# Meter-V2.net
KiCad netlist of a schematic drawn in EAGLE
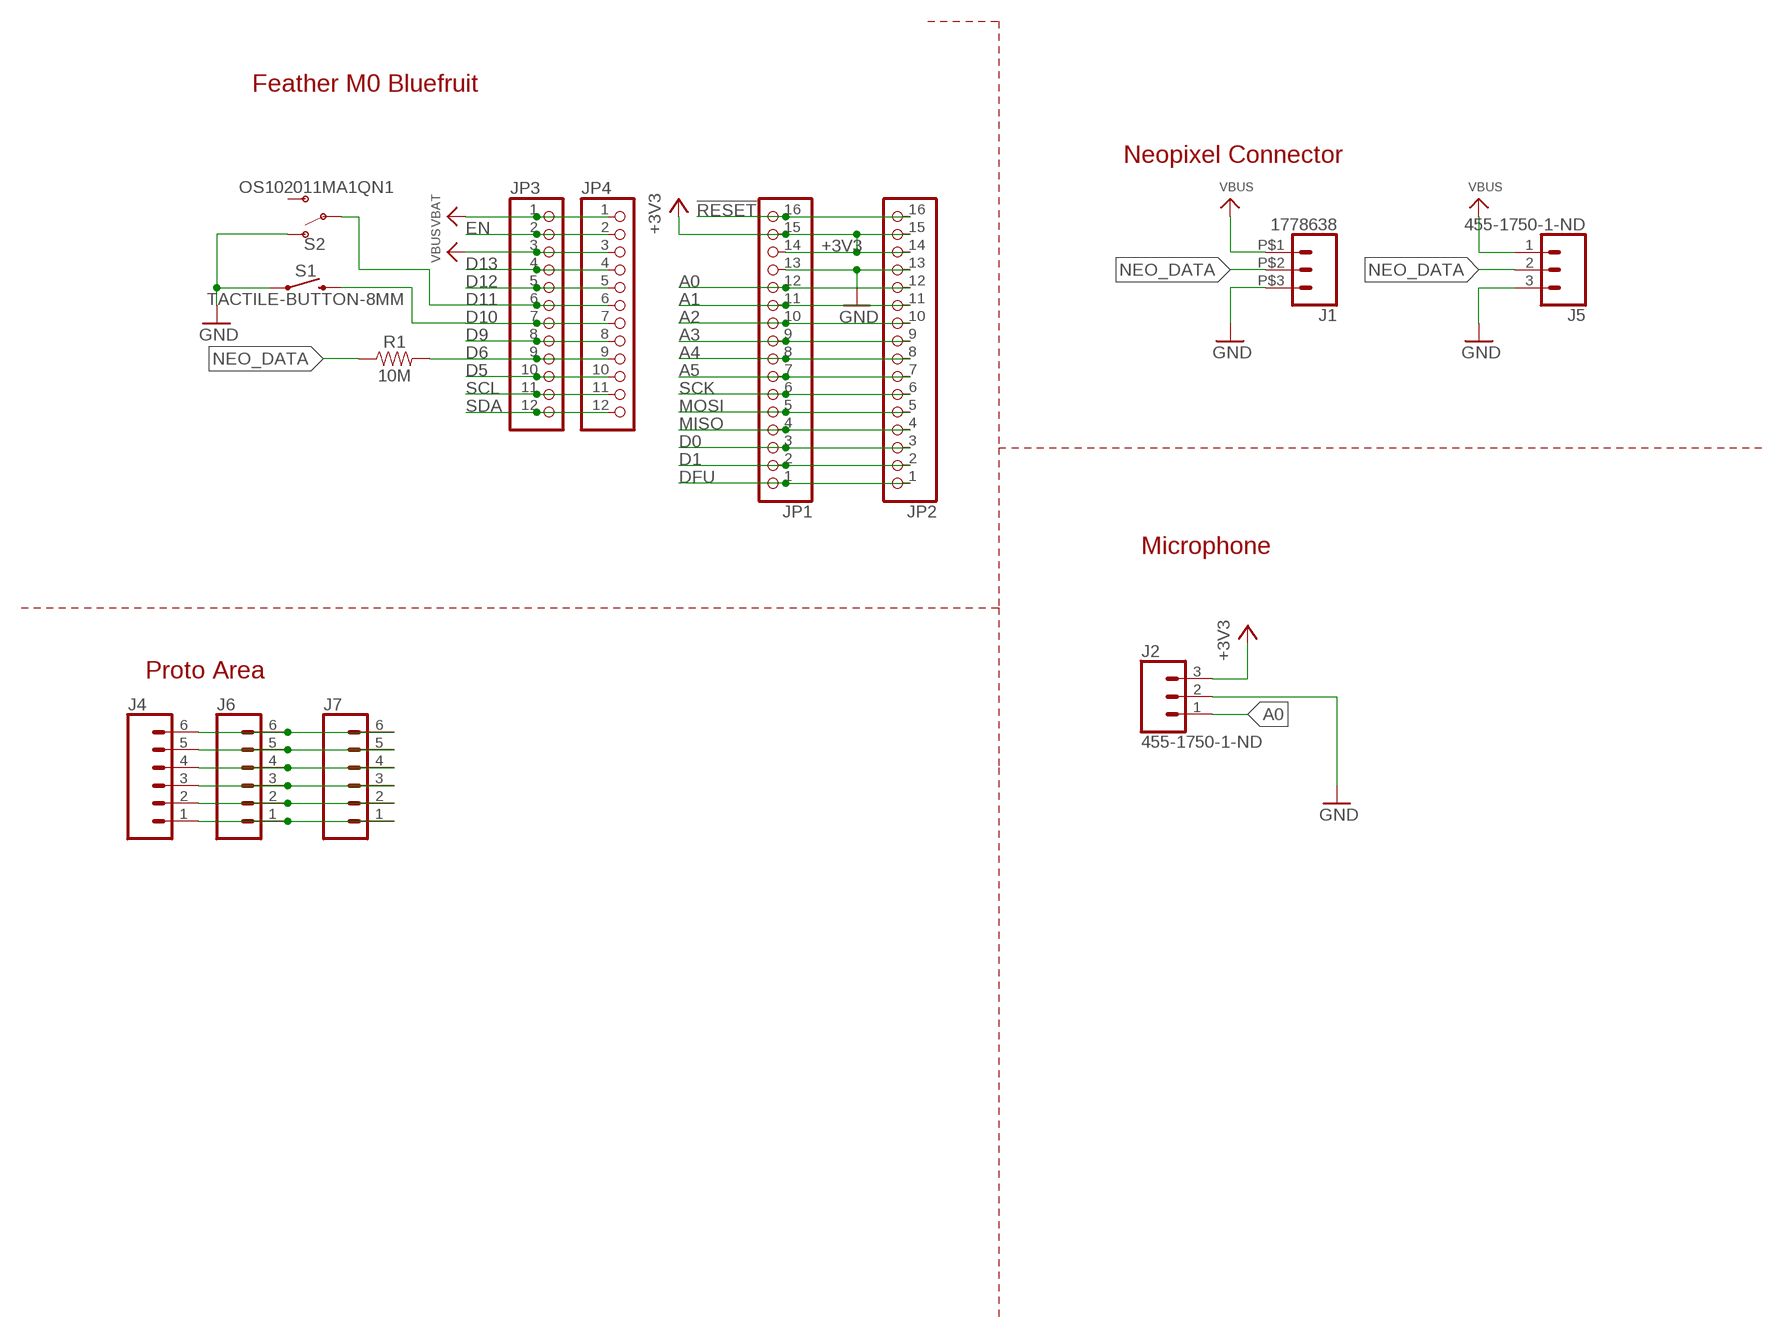
[diagram p0: schematic, sheet 1]

(export (version "E")
  (design (tool "Eeschema 10.0.6"))
  (components
    (comp (ref "J1")
      (value "1778638")
      (footprint "eagle-import:1778638")
      (libsource (lib "eagle-import") (part "1778638"))
    )
    (comp (ref "J2")
      (value "455-1750-1-ND")
      (footprint "eagle-import:1X03")
      (libsource (lib "eagle-import") (part "CONN_03"))
    )
    (comp (ref "J4")
      (value "CONN_06NO_SILK_NO_POP")
      (footprint "eagle-import:1X06_NO_SILK")
      (libsource (lib "eagle-import") (part "CONN_06NO_SILK_NO_POP"))
    )
    (comp (ref "J5")
      (value "455-1750-1-ND")
      (footprint "eagle-import:1X03")
      (libsource (lib "eagle-import") (part "CONN_03"))
    )
    (comp (ref "J6")
      (value "CONN_06NO_SILK_NO_POP")
      (footprint "eagle-import:1X06_NO_SILK")
      (libsource (lib "eagle-import") (part "CONN_06NO_SILK_NO_POP"))
    )
    (comp (ref "J7")
      (value "CONN_06NO_SILK_NO_POP")
      (footprint "eagle-import:1X06_NO_SILK")
      (libsource (lib "eagle-import") (part "CONN_06NO_SILK_NO_POP"))
    )
    (comp (ref "JP1")
      (value "HEADER-1X16ROUND")
      (footprint "eagle-import:1X16_ROUND")
      (libsource (lib "eagle-import") (part "HEADER-1X16ROUND"))
    )
    (comp (ref "JP2")
      (value "HEADER-1X16ROUND")
      (footprint "eagle-import:1X16_ROUND")
      (libsource (lib "eagle-import") (part "HEADER-1X16ROUND"))
    )
    (comp (ref "JP3")
      (value "HEADER-1X12")
      (footprint "eagle-import:1X12_ROUND")
      (libsource (lib "eagle-import") (part "HEADER-1X12"))
    )
    (comp (ref "JP4")
      (value "HEADER-1X12")
      (footprint "eagle-import:1X12_ROUND")
      (libsource (lib "eagle-import") (part "HEADER-1X12"))
    )
    (comp (ref "R1")
      (value "10M")
      (footprint "eagle-import:AXIAL-0.3")
      (libsource (lib "eagle-import") (part "10MOHM-HORIZ-1/4W-5%"))
    )
    (comp (ref "S1")
      (value "TACTILE-BUTTON-8MM")
      (footprint "eagle-import:BUTTON-8MM")
      (libsource (lib "eagle-import") (part "TACTILE-BUTTON-8MM"))
    )
    (comp (ref "S2")
      (value "OS102011MA1QN1")
      (footprint "eagle-import:OS102011MA1QN1")
      (libsource (lib "eagle-import") (part "OS102011MA1QN1"))
    )
  )
  (nets
    (net (code "1") (name "+3V3") (class "Default")
      (node (ref "J2") (pin "3") (pinfunction "3_3") (pintype "passive"))
      (node (ref "JP1") (pin "14") (pinfunction "14_14") (pintype "passive"))
      (node (ref "JP1") (pin "15") (pinfunction "15_15") (pintype "passive"))
      (node (ref "JP2") (pin "14") (pinfunction "14_14") (pintype "passive"))
      (node (ref "JP2") (pin "15") (pinfunction "15_15") (pintype "passive"))
    )
    (net (code "2") (name "/A1") (class "Default")
      (node (ref "JP1") (pin "11") (pinfunction "11_11") (pintype "passive"))
      (node (ref "JP2") (pin "11") (pinfunction "11_11") (pintype "passive"))
    )
    (net (code "3") (name "/A2") (class "Default")
      (node (ref "JP1") (pin "10") (pinfunction "10_10") (pintype "passive"))
      (node (ref "JP2") (pin "10") (pinfunction "10_10") (pintype "passive"))
    )
    (net (code "4") (name "/A3") (class "Default")
      (node (ref "JP1") (pin "9") (pinfunction "9_9") (pintype "passive"))
      (node (ref "JP2") (pin "9") (pinfunction "9_9") (pintype "passive"))
    )
    (net (code "5") (name "/A4") (class "Default")
      (node (ref "JP1") (pin "8") (pinfunction "8_8") (pintype "passive"))
      (node (ref "JP2") (pin "8") (pinfunction "8_8") (pintype "passive"))
    )
    (net (code "6") (name "/A5") (class "Default")
      (node (ref "JP1") (pin "7") (pinfunction "7_7") (pintype "passive"))
      (node (ref "JP2") (pin "7") (pinfunction "7_7") (pintype "passive"))
    )
    (net (code "7") (name "/D0") (class "Default")
      (node (ref "JP1") (pin "3") (pinfunction "3_3") (pintype "passive"))
      (node (ref "JP2") (pin "3") (pinfunction "3_3") (pintype "passive"))
    )
    (net (code "8") (name "/D1") (class "Default")
      (node (ref "JP1") (pin "2") (pinfunction "2_2") (pintype "passive"))
      (node (ref "JP2") (pin "2") (pinfunction "2_2") (pintype "passive"))
    )
    (net (code "9") (name "/D5") (class "Default")
      (node (ref "JP3") (pin "10") (pinfunction "10_10") (pintype "passive"))
      (node (ref "JP4") (pin "10") (pinfunction "10_10") (pintype "passive"))
    )
    (net (code "10") (name "/D6") (class "Default")
      (node (ref "JP3") (pin "9") (pinfunction "9_9") (pintype "passive"))
      (node (ref "JP4") (pin "9") (pinfunction "9_9") (pintype "passive"))
      (node (ref "R1") (pin "P$2") (pinfunction "2_P$2") (pintype "passive"))
    )
    (net (code "11") (name "/D9") (class "Default")
      (node (ref "JP3") (pin "8") (pinfunction "8_8") (pintype "passive"))
      (node (ref "JP4") (pin "8") (pinfunction "8_8") (pintype "passive"))
    )
    (net (code "12") (name "/D10") (class "Default")
      (node (ref "JP3") (pin "7") (pinfunction "7_7") (pintype "passive"))
      (node (ref "JP4") (pin "7") (pinfunction "7_7") (pintype "passive"))
      (node (ref "S1") (pin "P$2") (pinfunction "2_P$2") (pintype "passive"))
      (node (ref "S1") (pin "P$3") (pinfunction "2_P$3") (pintype "passive"))
    )
    (net (code "13") (name "/D11") (class "Default")
      (node (ref "JP3") (pin "6") (pinfunction "6_6") (pintype "passive"))
      (node (ref "JP4") (pin "6") (pinfunction "6_6") (pintype "passive"))
      (node (ref "S2") (pin "P$2") (pinfunction "P_P$2") (pintype "passive"))
    )
    (net (code "14") (name "/D12") (class "Default")
      (node (ref "JP3") (pin "5") (pinfunction "5_5") (pintype "passive"))
      (node (ref "JP4") (pin "5") (pinfunction "5_5") (pintype "passive"))
    )
    (net (code "15") (name "/D13") (class "Default")
      (node (ref "JP3") (pin "4") (pinfunction "4_4") (pintype "passive"))
      (node (ref "JP4") (pin "4") (pinfunction "4_4") (pintype "passive"))
    )
    (net (code "16") (name "/DFU") (class "Default")
      (node (ref "JP1") (pin "1") (pinfunction "1_1") (pintype "passive"))
      (node (ref "JP2") (pin "1") (pinfunction "1_1") (pintype "passive"))
    )
    (net (code "17") (name "/EN") (class "Default")
      (node (ref "JP3") (pin "2") (pinfunction "2_2") (pintype "passive"))
      (node (ref "JP4") (pin "2") (pinfunction "2_2") (pintype "passive"))
    )
    (net (code "18") (name "/MISO") (class "Default")
      (node (ref "JP1") (pin "4") (pinfunction "4_4") (pintype "passive"))
      (node (ref "JP2") (pin "4") (pinfunction "4_4") (pintype "passive"))
    )
    (net (code "19") (name "/MOSI") (class "Default")
      (node (ref "JP1") (pin "5") (pinfunction "5_5") (pintype "passive"))
      (node (ref "JP2") (pin "5") (pinfunction "5_5") (pintype "passive"))
    )
    (net (code "20") (name "/SCK") (class "Default")
      (node (ref "JP1") (pin "6") (pinfunction "6_6") (pintype "passive"))
      (node (ref "JP2") (pin "6") (pinfunction "6_6") (pintype "passive"))
    )
    (net (code "21") (name "/SCL") (class "Default")
      (node (ref "JP3") (pin "11") (pinfunction "11_11") (pintype "passive"))
      (node (ref "JP4") (pin "11") (pinfunction "11_11") (pintype "passive"))
    )
    (net (code "22") (name "/SDA") (class "Default")
      (node (ref "JP3") (pin "12") (pinfunction "12_12") (pintype "passive"))
      (node (ref "JP4") (pin "12") (pinfunction "12_12") (pintype "passive"))
    )
    (net (code "23") (name "/~{RESET}") (class "Default")
      (node (ref "JP1") (pin "16") (pinfunction "16_16") (pintype "passive"))
      (node (ref "JP2") (pin "16") (pinfunction "16_16") (pintype "passive"))
    )
    (net (code "24") (name "A0") (class "Default")
      (node (ref "J2") (pin "1") (pinfunction "1_1") (pintype "passive"))
      (node (ref "JP1") (pin "12") (pinfunction "12_12") (pintype "passive"))
      (node (ref "JP2") (pin "12") (pinfunction "12_12") (pintype "passive"))
    )
    (net (code "25") (name "GND") (class "Default")
      (node (ref "J1") (pin "P$3") (pinfunction "3_P$3") (pintype "passive"))
      (node (ref "J2") (pin "2") (pinfunction "2_2") (pintype "passive"))
      (node (ref "J5") (pin "3") (pinfunction "3_3") (pintype "passive"))
      (node (ref "JP1") (pin "13") (pinfunction "13_13") (pintype "passive"))
      (node (ref "JP2") (pin "13") (pinfunction "13_13") (pintype "passive"))
      (node (ref "S1") (pin "P$1") (pinfunction "1_P$1") (pintype "passive"))
      (node (ref "S1") (pin "P$4") (pinfunction "1_P$4") (pintype "passive"))
      (node (ref "S2") (pin "P$1") (pinfunction "O_P$1") (pintype "passive"))
    )
    (net (code "26") (name "NEO_DATA") (class "Default")
      (node (ref "J1") (pin "P$2") (pinfunction "2_P$2") (pintype "passive"))
      (node (ref "J5") (pin "2") (pinfunction "2_2") (pintype "passive"))
      (node (ref "R1") (pin "P$1") (pinfunction "1_P$1") (pintype "passive"))
    )
    (net (code "27") (name "Net-(J4-Pad1)") (class "Default")
      (node (ref "J4") (pin "1") (pinfunction "1_1") (pintype "passive"))
      (node (ref "J6") (pin "1") (pinfunction "1_1") (pintype "passive"))
      (node (ref "J7") (pin "1") (pinfunction "1_1") (pintype "passive"))
    )
    (net (code "28") (name "Net-(J4-Pad2)") (class "Default")
      (node (ref "J4") (pin "2") (pinfunction "2_2") (pintype "passive"))
      (node (ref "J6") (pin "2") (pinfunction "2_2") (pintype "passive"))
      (node (ref "J7") (pin "2") (pinfunction "2_2") (pintype "passive"))
    )
    (net (code "29") (name "Net-(J4-Pad3)") (class "Default")
      (node (ref "J4") (pin "3") (pinfunction "3_3") (pintype "passive"))
      (node (ref "J6") (pin "3") (pinfunction "3_3") (pintype "passive"))
      (node (ref "J7") (pin "3") (pinfunction "3_3") (pintype "passive"))
    )
    (net (code "30") (name "Net-(J4-Pad4)") (class "Default")
      (node (ref "J4") (pin "4") (pinfunction "4_4") (pintype "passive"))
      (node (ref "J6") (pin "4") (pinfunction "4_4") (pintype "passive"))
      (node (ref "J7") (pin "4") (pinfunction "4_4") (pintype "passive"))
    )
    (net (code "31") (name "Net-(J4-Pad5)") (class "Default")
      (node (ref "J4") (pin "5") (pinfunction "5_5") (pintype "passive"))
      (node (ref "J6") (pin "5") (pinfunction "5_5") (pintype "passive"))
      (node (ref "J7") (pin "5") (pinfunction "5_5") (pintype "passive"))
    )
    (net (code "32") (name "Net-(J4-Pad6)") (class "Default")
      (node (ref "J4") (pin "6") (pinfunction "6_6") (pintype "passive"))
      (node (ref "J6") (pin "6") (pinfunction "6_6") (pintype "passive"))
      (node (ref "J7") (pin "6") (pinfunction "6_6") (pintype "passive"))
    )
    (net (code "33") (name "VBAT") (class "Default")
      (node (ref "JP3") (pin "1") (pinfunction "1_1") (pintype "passive"))
      (node (ref "JP4") (pin "1") (pinfunction "1_1") (pintype "passive"))
    )
    (net (code "34") (name "VBUS") (class "Default")
      (node (ref "J1") (pin "P$1") (pinfunction "1_P$1") (pintype "passive"))
      (node (ref "J5") (pin "1") (pinfunction "1_1") (pintype "passive"))
      (node (ref "JP3") (pin "3") (pinfunction "3_3") (pintype "passive"))
      (node (ref "JP4") (pin "3") (pinfunction "3_3") (pintype "passive"))
    )
    (net (code "35") (name "unconnected-(S2-S-PadP$3)") (class "Default")
      (node (ref "S2") (pin "P$3") (pinfunction "S_P$3") (pintype "passive"))
    )
  )
)
